# 20x20_adapter_v3.net
KiCad netlist of a schematic drawn in EAGLE
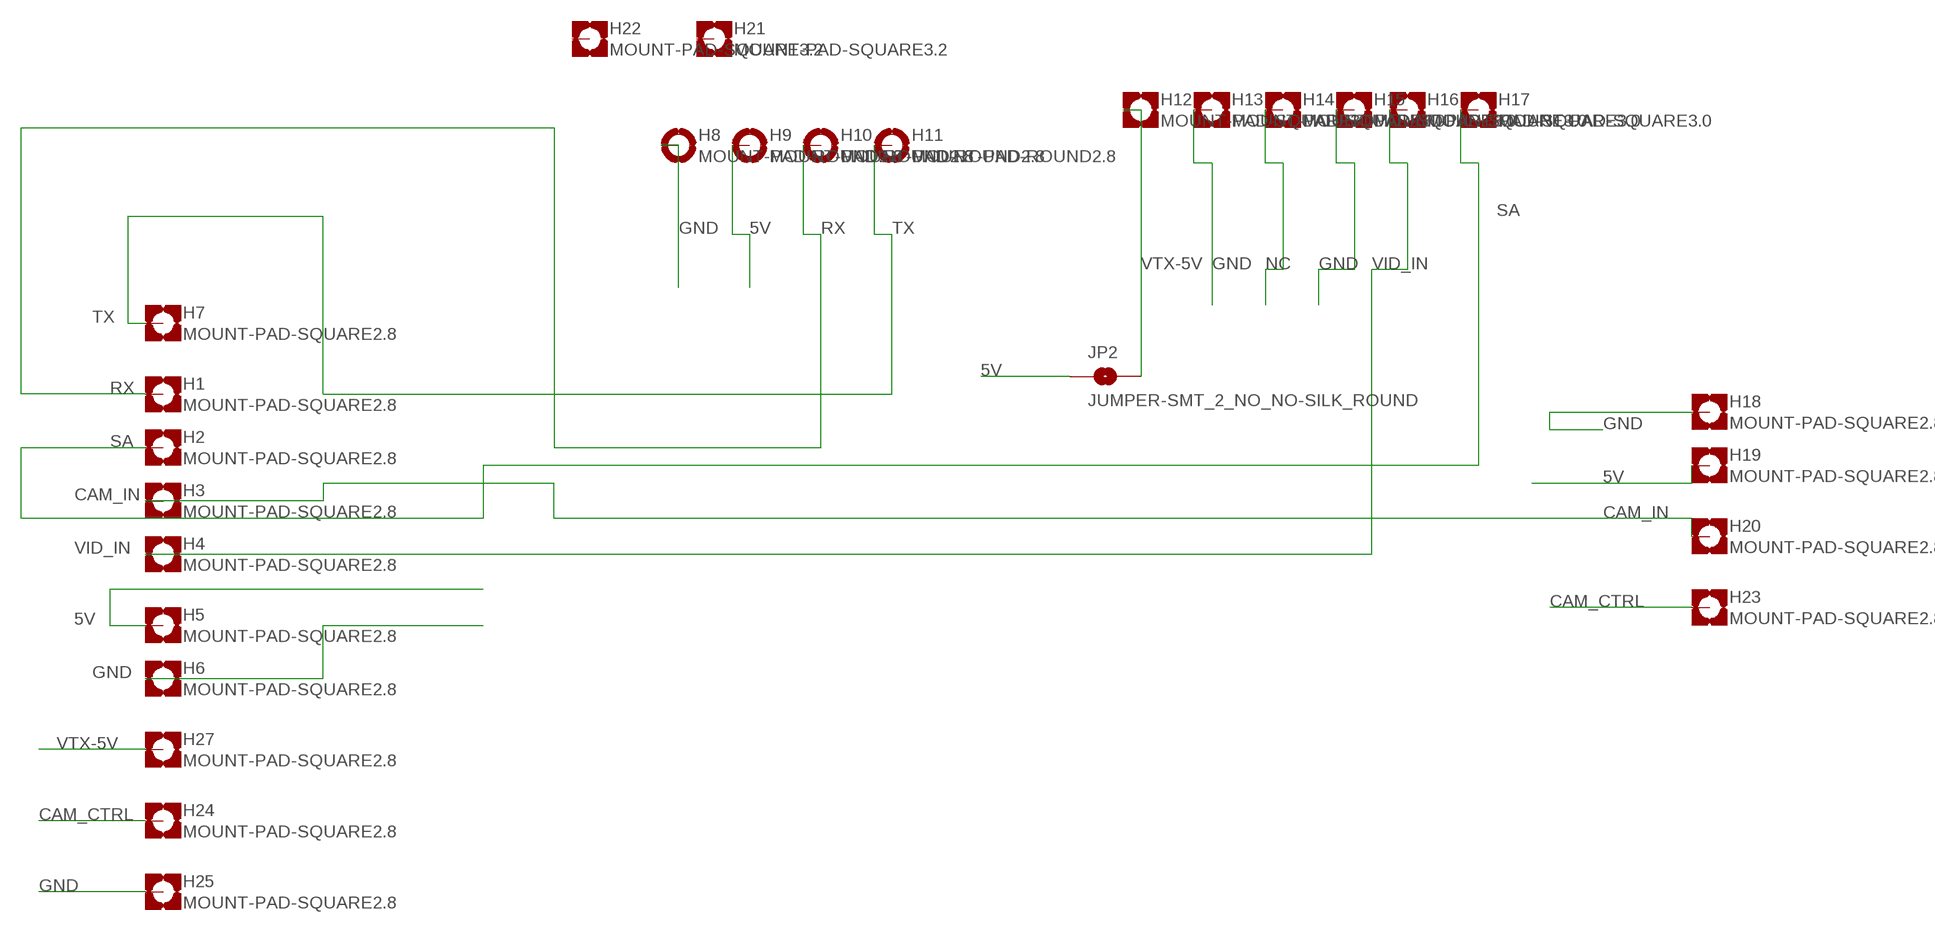
[diagram p0: schematic, sheet 1]

(export (version "E")
  (design (tool "Eeschema 10.0.6"))
  (components
    (comp (ref "H1")
      (value "MOUNT-PAD-SQUARE2.8")
      (footprint "eagle-import:2,8-PAD-SQUARE")
      (libsource (lib "eagle-import") (part "MOUNT-PAD-SQUARE2.8"))
    )
    (comp (ref "H2")
      (value "MOUNT-PAD-SQUARE2.8")
      (footprint "eagle-import:2,8-PAD-SQUARE")
      (libsource (lib "eagle-import") (part "MOUNT-PAD-SQUARE2.8"))
    )
    (comp (ref "H3")
      (value "MOUNT-PAD-SQUARE2.8")
      (footprint "eagle-import:2,8-PAD-SQUARE")
      (libsource (lib "eagle-import") (part "MOUNT-PAD-SQUARE2.8"))
    )
    (comp (ref "H4")
      (value "MOUNT-PAD-SQUARE2.8")
      (footprint "eagle-import:2,8-PAD-SQUARE")
      (libsource (lib "eagle-import") (part "MOUNT-PAD-SQUARE2.8"))
    )
    (comp (ref "H5")
      (value "MOUNT-PAD-SQUARE2.8")
      (footprint "eagle-import:2,8-PAD-SQUARE")
      (libsource (lib "eagle-import") (part "MOUNT-PAD-SQUARE2.8"))
    )
    (comp (ref "H6")
      (value "MOUNT-PAD-SQUARE2.8")
      (footprint "eagle-import:2,8-PAD-SQUARE")
      (libsource (lib "eagle-import") (part "MOUNT-PAD-SQUARE2.8"))
    )
    (comp (ref "H7")
      (value "MOUNT-PAD-SQUARE2.8")
      (footprint "eagle-import:2,8-PAD-SQUARE")
      (libsource (lib "eagle-import") (part "MOUNT-PAD-SQUARE2.8"))
    )
    (comp (ref "H8")
      (value "MOUNT-PAD-ROUND2.8")
      (footprint "eagle-import:1,0-PAD")
      (libsource (lib "eagle-import") (part "MOUNT-PAD-ROUND2.8"))
    )
    (comp (ref "H9")
      (value "MOUNT-PAD-ROUND2.8")
      (footprint "eagle-import:1,0-PAD")
      (libsource (lib "eagle-import") (part "MOUNT-PAD-ROUND2.8"))
    )
    (comp (ref "H10")
      (value "MOUNT-PAD-ROUND2.8")
      (footprint "eagle-import:1,0-PAD")
      (libsource (lib "eagle-import") (part "MOUNT-PAD-ROUND2.8"))
    )
    (comp (ref "H11")
      (value "MOUNT-PAD-ROUND2.8")
      (footprint "eagle-import:1,0-PAD")
      (libsource (lib "eagle-import") (part "MOUNT-PAD-ROUND2.8"))
    )
    (comp (ref "H12")
      (value "MOUNT-PAD-SQUARE3.0")
      (footprint "eagle-import:1,5-PAD-SQUARE")
      (libsource (lib "eagle-import") (part "MOUNT-PAD-SQUARE3.0"))
    )
    (comp (ref "H13")
      (value "MOUNT-PAD-SQUARE3.0")
      (footprint "eagle-import:1,5-PAD-SQUARE")
      (libsource (lib "eagle-import") (part "MOUNT-PAD-SQUARE3.0"))
    )
    (comp (ref "H14")
      (value "MOUNT-PAD-SQUARE3.0")
      (footprint "eagle-import:1,5-PAD-SQUARE")
      (libsource (lib "eagle-import") (part "MOUNT-PAD-SQUARE3.0"))
    )
    (comp (ref "H15")
      (value "MOUNT-PAD-SQUARE3.0")
      (footprint "eagle-import:1,5-PAD-SQUARE")
      (libsource (lib "eagle-import") (part "MOUNT-PAD-SQUARE3.0"))
    )
    (comp (ref "H16")
      (value "MOUNT-PAD-SQUARE3.0")
      (footprint "eagle-import:1,5-PAD-SQUARE")
      (libsource (lib "eagle-import") (part "MOUNT-PAD-SQUARE3.0"))
    )
    (comp (ref "H17")
      (value "MOUNT-PAD-SQUARE3.0")
      (footprint "eagle-import:1,5-PAD-SQUARE")
      (libsource (lib "eagle-import") (part "MOUNT-PAD-SQUARE3.0"))
    )
    (comp (ref "H18")
      (value "MOUNT-PAD-SQUARE2.8")
      (footprint "eagle-import:2,8-PAD-SQUARE")
      (libsource (lib "eagle-import") (part "MOUNT-PAD-SQUARE2.8"))
    )
    (comp (ref "H19")
      (value "MOUNT-PAD-SQUARE2.8")
      (footprint "eagle-import:2,8-PAD-SQUARE")
      (libsource (lib "eagle-import") (part "MOUNT-PAD-SQUARE2.8"))
    )
    (comp (ref "H20")
      (value "MOUNT-PAD-SQUARE2.8")
      (footprint "eagle-import:2,8-PAD-SQUARE")
      (libsource (lib "eagle-import") (part "MOUNT-PAD-SQUARE2.8"))
    )
    (comp (ref "H21")
      (value "MOUNT-PAD-SQUARE3.2")
      (footprint "eagle-import:3,2-PAD-SQUARE")
      (libsource (lib "eagle-import") (part "MOUNT-PAD-SQUARE3.2"))
    )
    (comp (ref "H22")
      (value "MOUNT-PAD-SQUARE3.2")
      (footprint "eagle-import:3,2-PAD-SQUARE")
      (libsource (lib "eagle-import") (part "MOUNT-PAD-SQUARE3.2"))
    )
    (comp (ref "H23")
      (value "MOUNT-PAD-SQUARE2.8")
      (footprint "eagle-import:2,8-PAD-SQUARE")
      (libsource (lib "eagle-import") (part "MOUNT-PAD-SQUARE2.8"))
    )
    (comp (ref "H24")
      (value "MOUNT-PAD-SQUARE2.8")
      (footprint "eagle-import:2,8-PAD-SQUARE")
      (libsource (lib "eagle-import") (part "MOUNT-PAD-SQUARE2.8"))
    )
    (comp (ref "H25")
      (value "MOUNT-PAD-SQUARE2.8")
      (footprint "eagle-import:2,8-PAD-SQUARE")
      (libsource (lib "eagle-import") (part "MOUNT-PAD-SQUARE2.8"))
    )
    (comp (ref "H27")
      (value "MOUNT-PAD-SQUARE2.8")
      (footprint "eagle-import:2,8-PAD-SQUARE")
      (libsource (lib "eagle-import") (part "MOUNT-PAD-SQUARE2.8"))
    )
    (comp (ref "JP2")
      (value "JUMPER-SMT_2_NO_NO-SILK_ROUND")
      (footprint "eagle-import:SMT-JUMPER_2_NO_NO-SILK_ROUND")
      (libsource (lib "eagle-import") (part "JUMPER-SMT_2_NO_NO-SILK_ROUND"))
    )
  )
  (nets
    (net (code "1") (name "/5V") (class "Default")
      (node (ref "H19") (pin "P$2") (pinfunction "MOUNT_P$2") (pintype "passive"))
      (node (ref "H5") (pin "P$2") (pinfunction "MOUNT_P$2") (pintype "passive"))
      (node (ref "H9") (pin "B1,0") (pinfunction "MOUNT_B1,0") (pintype "passive"))
      (node (ref "JP2") (pin "1") (pinfunction "1_1") (pintype "passive"))
    )
    (net (code "2") (name "/CAM_CTRL") (class "Default")
      (node (ref "H23") (pin "P$2") (pinfunction "MOUNT_P$2") (pintype "passive"))
      (node (ref "H24") (pin "P$2") (pinfunction "MOUNT_P$2") (pintype "passive"))
    )
    (net (code "3") (name "/CAM_IN") (class "Default")
      (node (ref "H20") (pin "P$2") (pinfunction "MOUNT_P$2") (pintype "passive"))
      (node (ref "H3") (pin "P$2") (pinfunction "MOUNT_P$2") (pintype "passive"))
    )
    (net (code "4") (name "/GND") (class "Default")
      (node (ref "H13") (pin "P$1") (pinfunction "MOUNT_P$1") (pintype "passive"))
      (node (ref "H15") (pin "P$1") (pinfunction "MOUNT_P$1") (pintype "passive"))
      (node (ref "H18") (pin "P$2") (pinfunction "MOUNT_P$2") (pintype "passive"))
      (node (ref "H25") (pin "P$2") (pinfunction "MOUNT_P$2") (pintype "passive"))
      (node (ref "H6") (pin "P$2") (pinfunction "MOUNT_P$2") (pintype "passive"))
      (node (ref "H8") (pin "B1,0") (pinfunction "MOUNT_B1,0") (pintype "passive"))
    )
    (net (code "5") (name "/NC") (class "Default")
      (node (ref "H14") (pin "P$1") (pinfunction "MOUNT_P$1") (pintype "passive"))
    )
    (net (code "6") (name "/RX") (class "Default")
      (node (ref "H1") (pin "P$2") (pinfunction "MOUNT_P$2") (pintype "passive"))
      (node (ref "H10") (pin "B1,0") (pinfunction "MOUNT_B1,0") (pintype "passive"))
    )
    (net (code "7") (name "/SA") (class "Default")
      (node (ref "H17") (pin "P$1") (pinfunction "MOUNT_P$1") (pintype "passive"))
      (node (ref "H2") (pin "P$2") (pinfunction "MOUNT_P$2") (pintype "passive"))
    )
    (net (code "8") (name "/TX") (class "Default")
      (node (ref "H11") (pin "B1,0") (pinfunction "MOUNT_B1,0") (pintype "passive"))
      (node (ref "H7") (pin "P$2") (pinfunction "MOUNT_P$2") (pintype "passive"))
    )
    (net (code "9") (name "/VID_IN") (class "Default")
      (node (ref "H16") (pin "P$1") (pinfunction "MOUNT_P$1") (pintype "passive"))
      (node (ref "H4") (pin "P$2") (pinfunction "MOUNT_P$2") (pintype "passive"))
    )
    (net (code "10") (name "/VTX-5V") (class "Default")
      (node (ref "H12") (pin "P$1") (pinfunction "MOUNT_P$1") (pintype "passive"))
      (node (ref "H27") (pin "P$2") (pinfunction "MOUNT_P$2") (pintype "passive"))
      (node (ref "JP2") (pin "2") (pinfunction "2_2") (pintype "passive"))
    )
    (net (code "11") (name "unconnected-(H21-MOUNT-PadP$1)") (class "Default")
      (node (ref "H21") (pin "P$1") (pinfunction "MOUNT_P$1") (pintype "passive"))
    )
    (net (code "12") (name "unconnected-(H22-MOUNT-PadP$1)") (class "Default")
      (node (ref "H22") (pin "P$1") (pinfunction "MOUNT_P$1") (pintype "passive"))
    )
  )
)
